# Power.net
KiCad netlist of a schematic drawn in Altium Designer
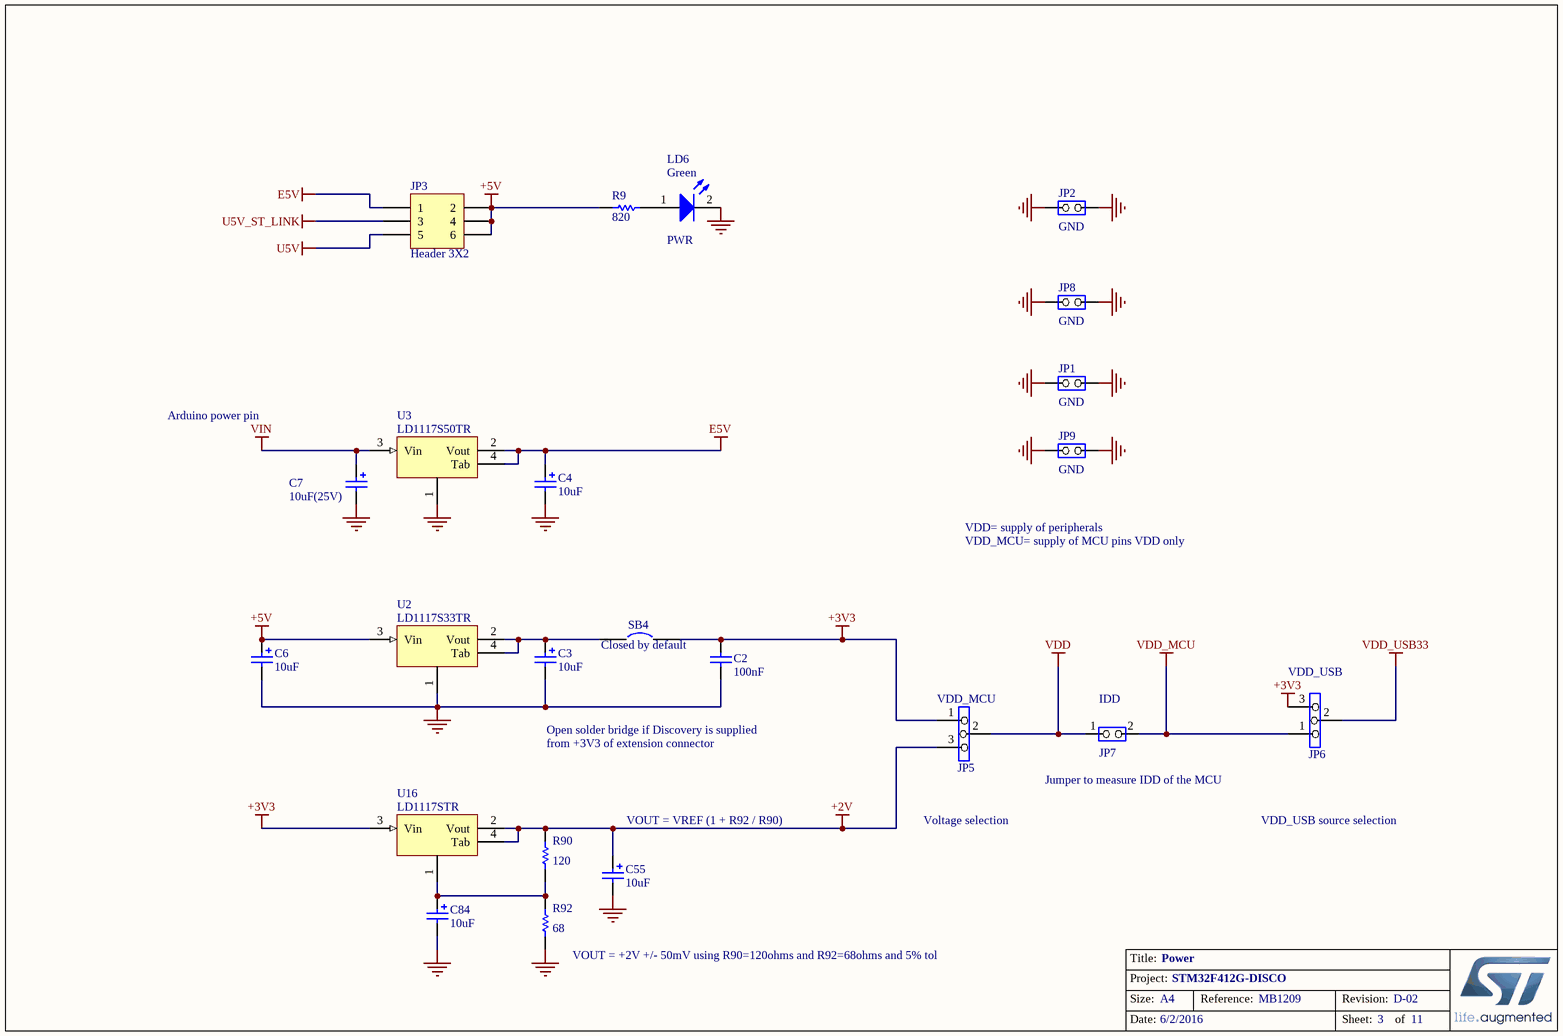
[diagram p0: Power.SchDoc]

(export (version "E")
  (design (tool "Eeschema 10.0.6"))
  (components
    (comp (ref "C2")
      (value "100nF")
      (footprint "0402C")
      (description "Capacitor")
      (fields (field (name "PUBLISHER") "Altium Limited"))
      (libsource (lib "Miscellaneous Devices") (part "Cap"))
    )
    (comp (ref "C3")
      (value "10uF")
      (footprint "TAN-A")
      (description "Polarized Capacitor (Radial)")
      (fields (field (name "PUBLISHER") "Altium Limited"))
      (libsource (lib "Miscellaneous Devices") (part "Cap Pol1"))
    )
    (comp (ref "C4")
      (value "10uF")
      (footprint "TAN-A")
      (description "Polarized Capacitor (Radial)")
      (fields (field (name "PUBLISHER") "Altium Limited"))
      (libsource (lib "Miscellaneous Devices") (part "Cap Pol1"))
    )
    (comp (ref "C6")
      (value "10uF")
      (footprint "TAN-A")
      (description "Polarized Capacitor (Radial)")
      (fields (field (name "PUBLISHER") "Altium Limited"))
      (libsource (lib "Miscellaneous Devices") (part "Cap Pol1"))
    )
    (comp (ref "C7")
      (value "10uF(25V)")
      (footprint "TAN-B")
      (description "Polarized Capacitor (Radial)")
      (fields (field (name "PUBLISHER") "Altium Limited"))
      (libsource (lib "Miscellaneous Devices") (part "Cap Pol1"))
    )
    (comp (ref "C55")
      (value "10uF")
      (footprint "TAN-A")
      (description "Polarized Capacitor (Radial)")
      (fields (field (name "PUBLISHER") "Altium Limited"))
      (libsource (lib "Miscellaneous Devices") (part "Cap Pol1"))
    )
    (comp (ref "C84")
      (value "10uF")
      (footprint "TAN-A")
      (description "Polarized Capacitor (Radial)")
      (fields (field (name "PUBLISHER") "Altium Limited"))
      (libsource (lib "Miscellaneous Devices") (part "Cap Pol1"))
    )
    (comp (ref "JP1")
      (value "Jumper2")
      (footprint "SIP2")
      (fields (field (name "SILKSCREEN") "GND"))
      (libsource (lib "*") (part "JP2"))
    )
    (comp (ref "JP2")
      (value "Jumper2")
      (footprint "SIP2")
      (fields (field (name "SILKSCREEN") "GND"))
      (libsource (lib "*") (part "JP2"))
    )
    (comp (ref "JP3")
      (value "Header 3X2")
      (footprint "HDR_2X3_2R54")
      (description "Header, 3-Pin, Dual row")
      (fields (field (name "PUBLISHER") "Altium Limited"))
      (libsource (lib "Miscellaneous Connectors") (part "Header 3X2"))
    )
    (comp (ref "JP5") (value "Jumper3") (footprint "SIP3") (libsource (lib "STR910_SCHLIB") (part "Jumper3")))
    (comp (ref "JP6") (value "Jumper3") (footprint "SIP3") (libsource (lib "STR910_SCHLIB") (part "Jumper3")))
    (comp (ref "JP7") (value "Jumper2") (footprint "SIP2") (libsource (lib "") (part "JP2_1")))
    (comp (ref "JP8")
      (value "Jumper2")
      (footprint "SIP2")
      (fields (field (name "SILKSCREEN") "GND"))
      (libsource (lib "*") (part "JP2"))
    )
    (comp (ref "JP9")
      (value "Jumper2")
      (footprint "SIP2")
      (fields (field (name "SILKSCREEN") "GND"))
      (libsource (lib "*") (part "JP2"))
    )
    (comp (ref "LD6")
      (value "Green")
      (footprint "0603D")
      (description "Typical RED, GREEN, YELLOW, AMBER GaAs LED")
      (fields (field (name "SILKSCREEN") "PWR") (field (name "PUBLISHER") "Altium Limited"))
      (libsource (lib "Miscellaneous Devices") (part "LED2"))
    )
    (comp (ref "R9")
      (value "820")
      (footprint "0402R")
      (description "Resistor")
      (fields (field (name "PUBLISHER") "Altium Limited"))
      (libsource (lib "Miscellaneous Devices") (part "res1"))
    )
    (comp (ref "R90")
      (value "120")
      (footprint "0603R")
      (description "Resistor")
      (fields (field (name "PUBLISHER") "Altium Limited"))
      (libsource (lib "Miscellaneous Devices") (part "res1"))
    )
    (comp (ref "R92")
      (value "68")
      (footprint "0603R")
      (description "Resistor")
      (fields (field (name "PUBLISHER") "Altium Limited"))
      (libsource (lib "Miscellaneous Devices") (part "res1"))
    )
    (comp (ref "SB4")
      (value "Closed by default")
      (footprint "SB_0603")
      (description "Circuit Breaker")
      (fields (field (name "PUBLISHER") "Altium Limited"))
      (libsource (lib "Miscellaneous Devices") (part "Circuit Breaker"))
    )
    (comp (ref "U2") (value "LD1117S33TR") (footprint "SOT-223") (libsource (lib "mb1045") (part "LD1117")))
    (comp (ref "U3") (value "LD1117S50TR") (footprint "SOT-223") (libsource (lib "mb1045") (part "LD1117")))
    (comp (ref "U16") (value "LD1117STR") (footprint "SOT-223") (libsource (lib "mb1045") (part "LD1117")))
  )
  (nets
    (net (code "1") (name "+2V") (class "Default")
      (node (ref "C55") (pin "1") (pinfunction "1_1") (pintype "passive"))
      (node (ref "JP5") (pin "3") (pintype "passive"))
      (node (ref "R90") (pin "1") (pinfunction "1_1") (pintype "passive"))
      (node (ref "U16") (pin "2") (pinfunction "Vout_2") (pintype "power_in"))
      (node (ref "U16") (pin "4") (pinfunction "Tab_4") (pintype "power_in"))
    )
    (net (code "2") (name "+3V3") (class "Default")
      (node (ref "C2") (pin "1") (pinfunction "1_1") (pintype "passive"))
      (node (ref "JP5") (pin "1") (pintype "passive"))
      (node (ref "JP6") (pin "3") (pintype "passive"))
      (node (ref "SB4") (pin "2") (pinfunction "2_2") (pintype "passive"))
      (node (ref "U16") (pin "3") (pinfunction "Vin_3") (pintype "input"))
    )
    (net (code "3") (name "+5V") (class "Default")
      (node (ref "C6") (pin "1") (pinfunction "1_1") (pintype "passive"))
      (node (ref "JP3") (pin "2") (pinfunction "2_2") (pintype "passive"))
      (node (ref "JP3") (pin "4") (pinfunction "4_4") (pintype "passive"))
      (node (ref "JP3") (pin "6") (pinfunction "6_6") (pintype "passive"))
      (node (ref "R9") (pin "2") (pinfunction "2_2") (pintype "passive"))
      (node (ref "U2") (pin "3") (pinfunction "Vin_3") (pintype "input"))
    )
    (net (code "4") (name "E5V") (class "Default")
      (node (ref "C4") (pin "1") (pinfunction "1_1") (pintype "passive"))
      (node (ref "JP3") (pin "1") (pinfunction "1_1") (pintype "passive"))
      (node (ref "U3") (pin "2") (pinfunction "Vout_2") (pintype "power_in"))
      (node (ref "U3") (pin "4") (pinfunction "Tab_4") (pintype "power_in"))
    )
    (net (code "5") (name "GND") (class "Default")
      (node (ref "C2") (pin "2") (pinfunction "2_2") (pintype "passive"))
      (node (ref "C3") (pin "2") (pinfunction "2_2") (pintype "passive"))
      (node (ref "C4") (pin "2") (pinfunction "2_2") (pintype "passive"))
      (node (ref "C55") (pin "2") (pinfunction "2_2") (pintype "passive"))
      (node (ref "C6") (pin "2") (pinfunction "2_2") (pintype "passive"))
      (node (ref "C7") (pin "2") (pinfunction "2_2") (pintype "passive"))
      (node (ref "C84") (pin "2") (pinfunction "2_2") (pintype "passive"))
      (node (ref "JP1") (pin "1") (pinfunction "COMMON_1") (pintype "passive"))
      (node (ref "JP1") (pin "2") (pinfunction "NO_2") (pintype "passive"))
      (node (ref "JP2") (pin "1") (pinfunction "COMMON_1") (pintype "passive"))
      (node (ref "JP2") (pin "2") (pinfunction "NO_2") (pintype "passive"))
      (node (ref "JP8") (pin "1") (pinfunction "COMMON_1") (pintype "passive"))
      (node (ref "JP8") (pin "2") (pinfunction "NO_2") (pintype "passive"))
      (node (ref "JP9") (pin "1") (pinfunction "COMMON_1") (pintype "passive"))
      (node (ref "JP9") (pin "2") (pinfunction "NO_2") (pintype "passive"))
      (node (ref "LD6") (pin "2") (pinfunction "K_2") (pintype "passive"))
      (node (ref "R92") (pin "2") (pinfunction "2_2") (pintype "passive"))
      (node (ref "U2") (pin "1") (pintype "passive"))
      (node (ref "U3") (pin "1") (pintype "passive"))
    )
    (net (code "6") (name "Net-(C84-Pad1)") (class "Default")
      (node (ref "C84") (pin "1") (pinfunction "1_1") (pintype "passive"))
      (node (ref "R90") (pin "2") (pinfunction "2_2") (pintype "passive"))
      (node (ref "R92") (pin "1") (pinfunction "1_1") (pintype "passive"))
      (node (ref "U16") (pin "1") (pintype "passive"))
    )
    (net (code "7") (name "Net-(LD6-A)") (class "Default")
      (node (ref "LD6") (pin "1") (pinfunction "A_1") (pintype "passive"))
      (node (ref "R9") (pin "1") (pinfunction "1_1") (pintype "passive"))
    )
    (net (code "8") (name "Net-(U2-Tab)") (class "Default")
      (node (ref "C3") (pin "1") (pinfunction "1_1") (pintype "passive"))
      (node (ref "SB4") (pin "1") (pinfunction "1_1") (pintype "passive"))
      (node (ref "U2") (pin "2") (pinfunction "Vout_2") (pintype "power_in"))
      (node (ref "U2") (pin "4") (pinfunction "Tab_4") (pintype "power_in"))
    )
    (net (code "9") (name "U5V") (class "Default")
      (node (ref "JP3") (pin "5") (pinfunction "5_5") (pintype "passive"))
    )
    (net (code "10") (name "U5V_ST_LINK") (class "Default")
      (node (ref "JP3") (pin "3") (pinfunction "3_3") (pintype "passive"))
    )
    (net (code "11") (name "VDD") (class "Default")
      (node (ref "JP5") (pin "2") (pintype "passive"))
      (node (ref "JP7") (pin "1") (pinfunction "COMMON_1") (pintype "passive"))
    )
    (net (code "12") (name "VDD_MCU") (class "Default")
      (node (ref "JP6") (pin "1") (pintype "passive"))
      (node (ref "JP7") (pin "2") (pinfunction "NO_2") (pintype "passive"))
    )
    (net (code "13") (name "VDD_USB33") (class "Default") (node (ref "JP6") (pin "2") (pintype "passive")))
    (net (code "14") (name "VIN") (class "Default")
      (node (ref "C7") (pin "1") (pinfunction "1_1") (pintype "passive"))
      (node (ref "U3") (pin "3") (pinfunction "Vin_3") (pintype "input"))
    )
  )
)
